# 09_USB_HDMI_sockets.net
KiCad netlist of a schematic drawn in Altium Designer
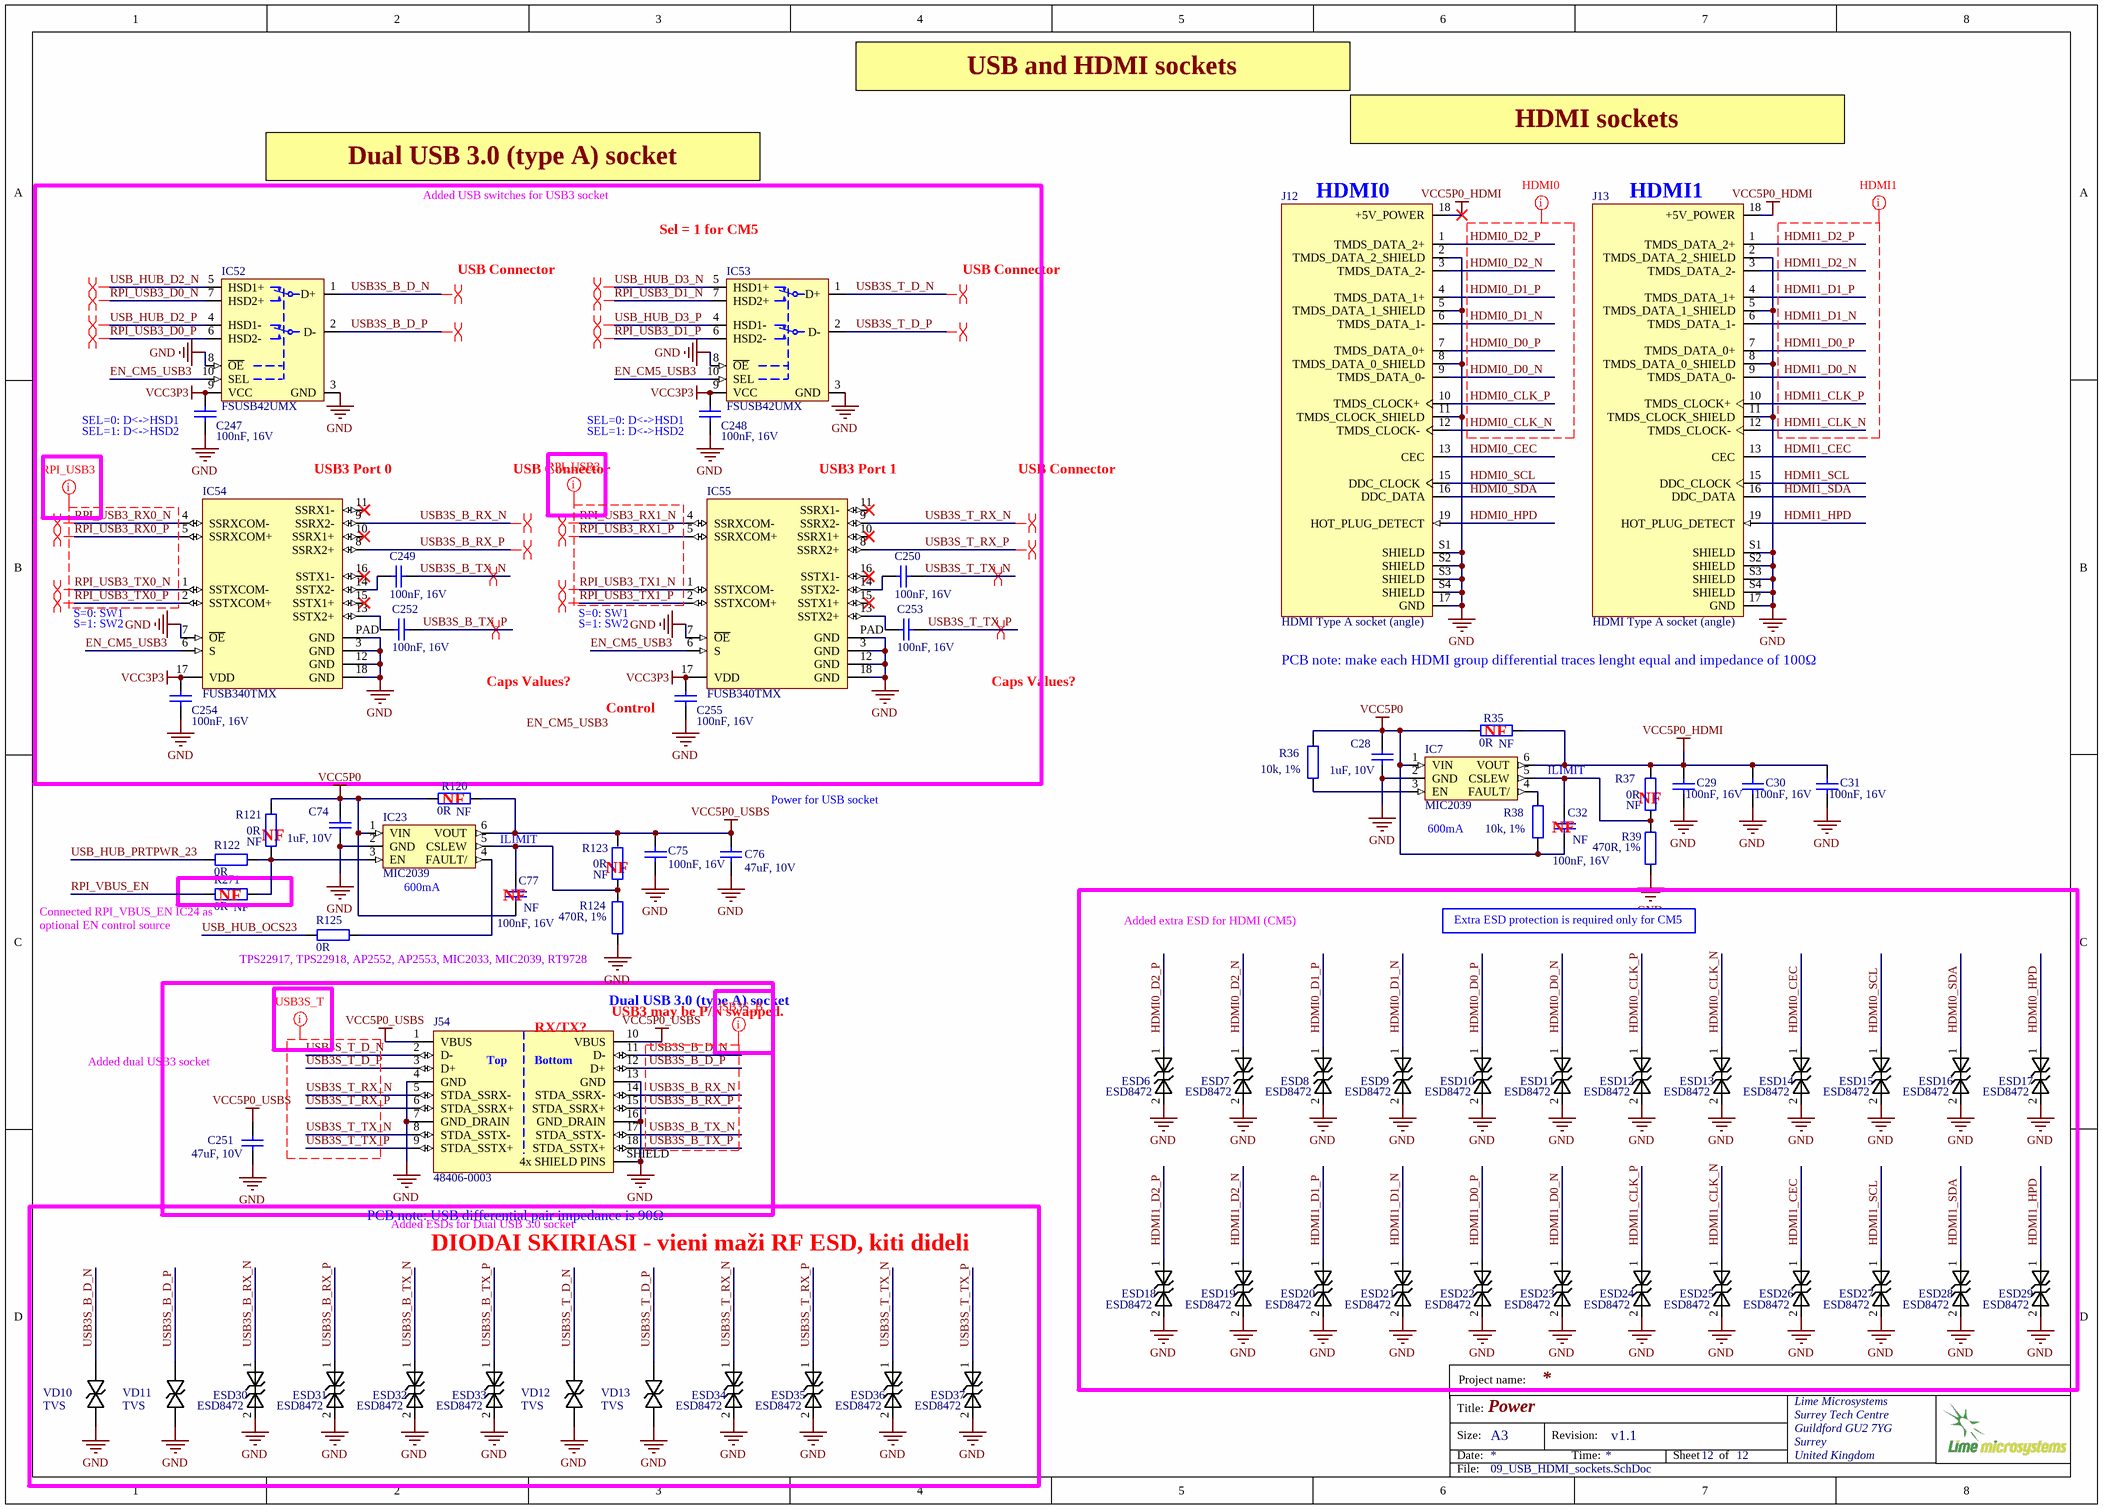
[diagram p0: 09_USB_HDMI_sockets.SchDoc]

(export (version "E")
  (design (tool "Eeschema 10.0.6"))
  (components
    (comp (ref "C28")
      (value "1uF, 10V")
      (footprint "CAP0402")
      (fields (field (name "MANUFACTURER") "Yageo"))
      (libsource (lib "") (part "Cap_0402_1"))
    )
    (comp (ref "C29")
      (value "100nF, 16V")
      (footprint "CAP0402")
      (fields
        (field (name "MANUFACTURER") "Murata Electronics")
        (field (name "TOLERANCE") "10 %")
        (field (name "MANUFACTURER PART NUMBER") "GRM155R71C104KA88D")
      )
      (libsource (lib "") (part "Cap_0402_1"))
    )
    (comp (ref "C30")
      (value "100nF, 16V")
      (footprint "CAP0402")
      (fields
        (field (name "MANUFACTURER") "Murata Electronics")
        (field (name "TOLERANCE") "10 %")
        (field (name "MANUFACTURER PART NUMBER") "GRM155R71C104KA88D")
      )
      (libsource (lib "") (part "Cap_0402_1"))
    )
    (comp (ref "C31")
      (value "100nF, 16V")
      (footprint "CAP0402")
      (fields
        (field (name "MANUFACTURER") "Murata Electronics")
        (field (name "TOLERANCE") "10 %")
        (field (name "MANUFACTURER PART NUMBER") "GRM155R71C104KA88D")
      )
      (libsource (lib "") (part "Cap_0402_1"))
    )
    (comp (ref "C32")
      (value "100nF, 16V")
      (footprint "CAP0402")
      (fields
        (field (name "ASSEMBLY INFO") "NF")
        (field (name "MANUFACTURER") "Murata Electronics")
        (field (name "TOLERANCE") "10 %")
        (field (name "MANUFACTURER PART NUMBER") "GRM155R71C104KA88D")
      )
      (libsource (lib "") (part "Cap_0402_1"))
    )
    (comp (ref "C74")
      (value "1uF, 10V")
      (footprint "CAP0402")
      (fields (field (name "MANUFACTURER") "Yageo"))
      (libsource (lib "") (part "Cap_0402_1"))
    )
    (comp (ref "C75")
      (value "100nF, 16V")
      (footprint "CAP0402")
      (fields
        (field (name "MANUFACTURER") "Murata Electronics")
        (field (name "TOLERANCE") "10 %")
        (field (name "MANUFACTURER PART NUMBER") "GRM155R71C104KA88D")
      )
      (libsource (lib "") (part "Cap_0402_1"))
    )
    (comp (ref "C76")
      (value "47uF, 10V")
      (footprint "CAP1206")
      (fields (field (name "TOLERANCE") "±20%") (field (name "MANUFACTURER") "TDK Corporation"))
      (libsource (lib "LimeFPGAboard_schLib") (part "Cap_1206"))
    )
    (comp (ref "C77")
      (value "100nF, 16V")
      (footprint "CAP0402")
      (fields
        (field (name "ASSEMBLY INFO") "NF")
        (field (name "MANUFACTURER") "Murata Electronics")
        (field (name "TOLERANCE") "10 %")
        (field (name "MANUFACTURER PART NUMBER") "GRM155R71C104KA88D")
      )
      (libsource (lib "") (part "Cap_0402_1"))
    )
    (comp (ref "C247")
      (value "100nF, 16V")
      (footprint "CAP0402")
      (fields
        (field (name "MANUFACTURER") "Murata Electronics")
        (field (name "TOLERANCE") "10 %")
        (field (name "MANUFACTURER PART NUMBER") "GRM155R71C104KA88D")
      )
      (libsource (lib "LimeMicroAltiumLib_schLib") (part "Cap_0402"))
    )
    (comp (ref "C248")
      (value "100nF, 16V")
      (footprint "CAP0402")
      (fields
        (field (name "MANUFACTURER") "Murata Electronics")
        (field (name "TOLERANCE") "10 %")
        (field (name "MANUFACTURER PART NUMBER") "GRM155R71C104KA88D")
      )
      (libsource (lib "LimeMicroAltiumLib_schLib") (part "Cap_0402"))
    )
    (comp (ref "C249")
      (value "100nF, 16V")
      (footprint "CAP0402")
      (fields
        (field (name "MANUFACTURER") "Murata Electronics")
        (field (name "TOLERANCE") "10 %")
        (field (name "MANUFACTURER PART NUMBER") "GRM155R71C104KA88D")
      )
      (libsource (lib "LimeMicroAltiumLib_schLib") (part "Cap_0402"))
    )
    (comp (ref "C250")
      (value "100nF, 16V")
      (footprint "CAP0402")
      (fields
        (field (name "MANUFACTURER") "Murata Electronics")
        (field (name "TOLERANCE") "10 %")
        (field (name "MANUFACTURER PART NUMBER") "GRM155R71C104KA88D")
      )
      (libsource (lib "LimeMicroAltiumLib_schLib") (part "Cap_0402"))
    )
    (comp (ref "C251")
      (value "47uF, 10V")
      (footprint "CAP1206")
      (fields (field (name "TOLERANCE") "±20%") (field (name "MANUFACTURER") "TDK Corporation"))
      (libsource (lib "LimeFPGAboard_schLib") (part "Cap_1206"))
    )
    (comp (ref "C252")
      (value "100nF, 16V")
      (footprint "CAP0402")
      (fields
        (field (name "MANUFACTURER") "Murata Electronics")
        (field (name "TOLERANCE") "10 %")
        (field (name "MANUFACTURER PART NUMBER") "GRM155R71C104KA88D")
      )
      (libsource (lib "LimeMicroAltiumLib_schLib") (part "Cap_0402"))
    )
    (comp (ref "C253")
      (value "100nF, 16V")
      (footprint "CAP0402")
      (fields
        (field (name "MANUFACTURER") "Murata Electronics")
        (field (name "TOLERANCE") "10 %")
        (field (name "MANUFACTURER PART NUMBER") "GRM155R71C104KA88D")
      )
      (libsource (lib "LimeMicroAltiumLib_schLib") (part "Cap_0402"))
    )
    (comp (ref "C254")
      (value "100nF, 16V")
      (footprint "CAP0402")
      (fields
        (field (name "MANUFACTURER") "Murata Electronics")
        (field (name "TOLERANCE") "10 %")
        (field (name "MANUFACTURER PART NUMBER") "GRM155R71C104KA88D")
      )
      (libsource (lib "LimeMicroAltiumLib_schLib") (part "Cap_0402"))
    )
    (comp (ref "C255")
      (value "100nF, 16V")
      (footprint "CAP0402")
      (fields
        (field (name "MANUFACTURER") "Murata Electronics")
        (field (name "TOLERANCE") "10 %")
        (field (name "MANUFACTURER PART NUMBER") "GRM155R71C104KA88D")
      )
      (libsource (lib "LimeMicroAltiumLib_schLib") (part "Cap_0402"))
    )
    (comp (ref "ESD6")
      (value "ESD8472")
      (footprint "ESD8472_X3DFN2")
      (fields (field (name "MANUFACTURER") "ON Semiconductor"))
      (libsource (lib "LimeMicroAltiumLib_schLib") (part "ESD8472"))
    )
    (comp (ref "ESD7")
      (value "ESD8472")
      (footprint "ESD8472_X3DFN2")
      (fields (field (name "MANUFACTURER") "ON Semiconductor"))
      (libsource (lib "LimeMicroAltiumLib_schLib") (part "ESD8472"))
    )
    (comp (ref "ESD8")
      (value "ESD8472")
      (footprint "ESD8472_X3DFN2")
      (fields (field (name "MANUFACTURER") "ON Semiconductor"))
      (libsource (lib "LimeMicroAltiumLib_schLib") (part "ESD8472"))
    )
    (comp (ref "ESD9")
      (value "ESD8472")
      (footprint "ESD8472_X3DFN2")
      (fields (field (name "MANUFACTURER") "ON Semiconductor"))
      (libsource (lib "LimeMicroAltiumLib_schLib") (part "ESD8472"))
    )
    (comp (ref "ESD10")
      (value "ESD8472")
      (footprint "ESD8472_X3DFN2")
      (fields (field (name "MANUFACTURER") "ON Semiconductor"))
      (libsource (lib "LimeMicroAltiumLib_schLib") (part "ESD8472"))
    )
    (comp (ref "ESD11")
      (value "ESD8472")
      (footprint "ESD8472_X3DFN2")
      (fields (field (name "MANUFACTURER") "ON Semiconductor"))
      (libsource (lib "LimeMicroAltiumLib_schLib") (part "ESD8472"))
    )
    (comp (ref "ESD12")
      (value "ESD8472")
      (footprint "ESD8472_X3DFN2")
      (fields (field (name "MANUFACTURER") "ON Semiconductor"))
      (libsource (lib "LimeMicroAltiumLib_schLib") (part "ESD8472"))
    )
    (comp (ref "ESD13")
      (value "ESD8472")
      (footprint "ESD8472_X3DFN2")
      (fields (field (name "MANUFACTURER") "ON Semiconductor"))
      (libsource (lib "LimeMicroAltiumLib_schLib") (part "ESD8472"))
    )
    (comp (ref "ESD14")
      (value "ESD8472")
      (footprint "ESD8472_X3DFN2")
      (fields (field (name "MANUFACTURER") "ON Semiconductor"))
      (libsource (lib "LimeMicroAltiumLib_schLib") (part "ESD8472"))
    )
    (comp (ref "ESD15")
      (value "ESD8472")
      (footprint "ESD8472_X3DFN2")
      (fields (field (name "MANUFACTURER") "ON Semiconductor"))
      (libsource (lib "LimeMicroAltiumLib_schLib") (part "ESD8472"))
    )
    (comp (ref "ESD16")
      (value "ESD8472")
      (footprint "ESD8472_X3DFN2")
      (fields (field (name "MANUFACTURER") "ON Semiconductor"))
      (libsource (lib "LimeMicroAltiumLib_schLib") (part "ESD8472"))
    )
    (comp (ref "ESD17")
      (value "ESD8472")
      (footprint "ESD8472_X3DFN2")
      (fields (field (name "MANUFACTURER") "ON Semiconductor"))
      (libsource (lib "LimeMicroAltiumLib_schLib") (part "ESD8472"))
    )
    (comp (ref "ESD18")
      (value "ESD8472")
      (footprint "ESD8472_X3DFN2")
      (fields (field (name "MANUFACTURER") "ON Semiconductor"))
      (libsource (lib "LimeMicroAltiumLib_schLib") (part "ESD8472"))
    )
    (comp (ref "ESD19")
      (value "ESD8472")
      (footprint "ESD8472_X3DFN2")
      (fields (field (name "MANUFACTURER") "ON Semiconductor"))
      (libsource (lib "LimeMicroAltiumLib_schLib") (part "ESD8472"))
    )
    (comp (ref "ESD20")
      (value "ESD8472")
      (footprint "ESD8472_X3DFN2")
      (fields (field (name "MANUFACTURER") "ON Semiconductor"))
      (libsource (lib "LimeMicroAltiumLib_schLib") (part "ESD8472"))
    )
    (comp (ref "ESD21")
      (value "ESD8472")
      (footprint "ESD8472_X3DFN2")
      (fields (field (name "MANUFACTURER") "ON Semiconductor"))
      (libsource (lib "LimeMicroAltiumLib_schLib") (part "ESD8472"))
    )
    (comp (ref "ESD22")
      (value "ESD8472")
      (footprint "ESD8472_X3DFN2")
      (fields (field (name "MANUFACTURER") "ON Semiconductor"))
      (libsource (lib "LimeMicroAltiumLib_schLib") (part "ESD8472"))
    )
    (comp (ref "ESD23")
      (value "ESD8472")
      (footprint "ESD8472_X3DFN2")
      (fields (field (name "MANUFACTURER") "ON Semiconductor"))
      (libsource (lib "LimeMicroAltiumLib_schLib") (part "ESD8472"))
    )
    (comp (ref "ESD24")
      (value "ESD8472")
      (footprint "ESD8472_X3DFN2")
      (fields (field (name "MANUFACTURER") "ON Semiconductor"))
      (libsource (lib "LimeMicroAltiumLib_schLib") (part "ESD8472"))
    )
    (comp (ref "ESD25")
      (value "ESD8472")
      (footprint "ESD8472_X3DFN2")
      (fields (field (name "MANUFACTURER") "ON Semiconductor"))
      (libsource (lib "LimeMicroAltiumLib_schLib") (part "ESD8472"))
    )
    (comp (ref "ESD26")
      (value "ESD8472")
      (footprint "ESD8472_X3DFN2")
      (fields (field (name "MANUFACTURER") "ON Semiconductor"))
      (libsource (lib "LimeMicroAltiumLib_schLib") (part "ESD8472"))
    )
    (comp (ref "ESD27")
      (value "ESD8472")
      (footprint "ESD8472_X3DFN2")
      (fields (field (name "MANUFACTURER") "ON Semiconductor"))
      (libsource (lib "LimeMicroAltiumLib_schLib") (part "ESD8472"))
    )
    (comp (ref "ESD28")
      (value "ESD8472")
      (footprint "ESD8472_X3DFN2")
      (fields (field (name "MANUFACTURER") "ON Semiconductor"))
      (libsource (lib "LimeMicroAltiumLib_schLib") (part "ESD8472"))
    )
    (comp (ref "ESD29")
      (value "ESD8472")
      (footprint "ESD8472_X3DFN2")
      (fields (field (name "MANUFACTURER") "ON Semiconductor"))
      (libsource (lib "LimeMicroAltiumLib_schLib") (part "ESD8472"))
    )
    (comp (ref "ESD30")
      (value "ESD8472")
      (footprint "ESD8472_X3DFN2")
      (fields (field (name "MANUFACTURER") "ON Semiconductor"))
      (libsource (lib "LimeMicroAltiumLib_schLib") (part "ESD8472"))
    )
    (comp (ref "ESD31")
      (value "ESD8472")
      (footprint "ESD8472_X3DFN2")
      (fields (field (name "MANUFACTURER") "ON Semiconductor"))
      (libsource (lib "LimeMicroAltiumLib_schLib") (part "ESD8472"))
    )
    (comp (ref "ESD32")
      (value "ESD8472")
      (footprint "ESD8472_X3DFN2")
      (fields (field (name "MANUFACTURER") "ON Semiconductor"))
      (libsource (lib "LimeMicroAltiumLib_schLib") (part "ESD8472"))
    )
    (comp (ref "ESD33")
      (value "ESD8472")
      (footprint "ESD8472_X3DFN2")
      (fields (field (name "MANUFACTURER") "ON Semiconductor"))
      (libsource (lib "LimeMicroAltiumLib_schLib") (part "ESD8472"))
    )
    (comp (ref "ESD34")
      (value "ESD8472")
      (footprint "ESD8472_X3DFN2")
      (fields (field (name "MANUFACTURER") "ON Semiconductor"))
      (libsource (lib "LimeMicroAltiumLib_schLib") (part "ESD8472"))
    )
    (comp (ref "ESD35")
      (value "ESD8472")
      (footprint "ESD8472_X3DFN2")
      (fields (field (name "MANUFACTURER") "ON Semiconductor"))
      (libsource (lib "LimeMicroAltiumLib_schLib") (part "ESD8472"))
    )
    (comp (ref "ESD36")
      (value "ESD8472")
      (footprint "ESD8472_X3DFN2")
      (fields (field (name "MANUFACTURER") "ON Semiconductor"))
      (libsource (lib "LimeMicroAltiumLib_schLib") (part "ESD8472"))
    )
    (comp (ref "ESD37")
      (value "ESD8472")
      (footprint "ESD8472_X3DFN2")
      (fields (field (name "MANUFACTURER") "ON Semiconductor"))
      (libsource (lib "LimeMicroAltiumLib_schLib") (part "ESD8472"))
    )
    (comp (ref "IC7")
      (value "MIC2039")
      (footprint "SOT23-6")
      (fields (field (name "MANUFACTURER") "Microchip"))
      (libsource (lib "LimeMicroAltiumLib_schLib_r04") (part "MIC2033_power_switch"))
    )
    (comp (ref "IC23")
      (value "MIC2039")
      (footprint "SOT23-6")
      (fields (field (name "MANUFACTURER") "Microchip"))
      (libsource (lib "LimeMicroAltiumLib_schLib_r04") (part "MIC2033_power_switch"))
    )
    (comp (ref "IC52")
      (value "FSUSB42UMX")
      (footprint "FSUSB42UMX")
      (fields (field (name "MANUFACTURER") "ON Semiconductor") (field (name "BASE PART NUMBER") "FSUSB42"))
      (libsource (lib "LimeMicroAltiumLib_schLib_r01") (part "FSUSB42UMX"))
    )
    (comp (ref "IC53")
      (value "FSUSB42UMX")
      (footprint "FSUSB42UMX")
      (fields (field (name "MANUFACTURER") "ON Semiconductor") (field (name "BASE PART NUMBER") "FSUSB42"))
      (libsource (lib "LimeMicroAltiumLib_schLib_r01") (part "FSUSB42UMX"))
    )
    (comp (ref "IC54")
      (value "FUSB340TMX")
      (footprint "FUSB340TMX_USB_switch_18-XFQFN")
      (fields (field (name "MANUFACTURER") "ON Semiconductor / Fairchild"))
      (libsource (lib "LimeMicroAltiumLib") (part "FUSB340TMX_USB_switch"))
    )
    (comp (ref "IC55")
      (value "FUSB340TMX")
      (footprint "FUSB340TMX_USB_switch_18-XFQFN")
      (fields (field (name "MANUFACTURER") "ON Semiconductor / Fairchild"))
      (libsource (lib "LimeMicroAltiumLib") (part "FUSB340TMX_USB_switch"))
    )
    (comp (ref "J12")
      (value "HDMI Type A socket (angle)")
      (footprint "HDMI_HD01-19-RA-TH")
      (fields (field (name "MANUFACTURER") "CUI Devices"))
      (libsource (lib "LimeMicroAltiumLib_schLib_r04") (part "HDMI_HD01-19-RA-TH"))
    )
    (comp (ref "J13")
      (value "HDMI Type A socket (angle)")
      (footprint "HDMI_HD01-19-RA-TH")
      (fields (field (name "MANUFACTURER") "CUI Devices"))
      (libsource (lib "LimeMicroAltiumLib_schLib_r04") (part "HDMI_HD01-19-RA-TH"))
    )
    (comp (ref "J54")
      (value "48406-0003")
      (footprint "Dual_USB_48406-0003_Molex")
      (fields (field (name "MANUFACTURER") "Molex"))
      (libsource (lib "LimeMicroAltiumLib") (part "Dual_USB_48406-0003_Molex"))
    )
    (comp (ref "R35")
      (value "0R")
      (footprint "RES0402")
      (fields
        (field (name "ASSEMBLY INFO") "NF")
        (field (name "MANUFACTURER") "Yageo")
        (field (name "TOLERANCE") "Jumper")
      )
      (libsource (lib "LimeMicroAltiumLib_schLib") (part "Res_0402"))
    )
    (comp (ref "R36")
      (value "10k, 1%")
      (footprint "RES0402")
      (fields (field (name "MANUFACTURER") "Yageo") (field (name "TOLERANCE") "±1%"))
      (libsource (lib "") (part "Res_0402_1"))
    )
    (comp (ref "R37")
      (value "0R")
      (footprint "RES0402")
      (fields
        (field (name "ASSEMBLY INFO") "NF")
        (field (name "MANUFACTURER") "Yageo")
        (field (name "TOLERANCE") "Jumper")
      )
      (libsource (lib "LimeMicroAltiumLib_schLib") (part "Res_0402"))
    )
    (comp (ref "R38")
      (value "10k, 1%")
      (footprint "RES0402")
      (fields (field (name "MANUFACTURER") "Yageo") (field (name "TOLERANCE") "±1%"))
      (libsource (lib "") (part "Res_0402_1"))
    )
    (comp (ref "R39")
      (value "470R, 1%")
      (footprint "RES0402")
      (fields (field (name "TOLERANCE") "1%") (field (name "MANUFACTURER") "Yageo"))
      (libsource (lib "LimeMicroAltiumLib_schLib") (part "Res_0402"))
    )
    (comp (ref "R120")
      (value "0R")
      (footprint "RES0402")
      (fields
        (field (name "ASSEMBLY INFO") "NF")
        (field (name "MANUFACTURER") "Yageo")
        (field (name "TOLERANCE") "Jumper")
      )
      (libsource (lib "LimeMicroAltiumLib_schLib") (part "Res_0402"))
    )
    (comp (ref "R121")
      (value "0R")
      (footprint "RES0402")
      (fields
        (field (name "ASSEMBLY INFO") "NF")
        (field (name "MANUFACTURER") "Yageo")
        (field (name "TOLERANCE") "Jumper")
      )
      (libsource (lib "LimeMicroAltiumLib_schLib") (part "Res_0402"))
    )
    (comp (ref "R122")
      (value "0R")
      (footprint "RES0402")
      (fields (field (name "MANUFACTURER") "Yageo") (field (name "TOLERANCE") "Jumper"))
      (libsource (lib "LimeMicroAltiumLib_schLib") (part "Res_0402"))
    )
    (comp (ref "R123")
      (value "0R")
      (footprint "RES0402")
      (fields
        (field (name "ASSEMBLY INFO") "NF")
        (field (name "MANUFACTURER") "Yageo")
        (field (name "TOLERANCE") "Jumper")
      )
      (libsource (lib "LimeMicroAltiumLib_schLib") (part "Res_0402"))
    )
    (comp (ref "R124")
      (value "470R, 1%")
      (footprint "RES0402")
      (fields (field (name "TOLERANCE") "1%") (field (name "MANUFACTURER") "Yageo"))
      (libsource (lib "LimeMicroAltiumLib_schLib") (part "Res_0402"))
    )
    (comp (ref "R125")
      (value "0R")
      (footprint "RES0402")
      (fields (field (name "MANUFACTURER") "Yageo") (field (name "TOLERANCE") "Jumper"))
      (libsource (lib "LimeMicroAltiumLib_schLib") (part "Res_0402"))
    )
    (comp (ref "R271")
      (value "0R")
      (footprint "RES0402")
      (fields
        (field (name "ASSEMBLY INFO") "NF")
        (field (name "MANUFACTURER") "Yageo")
        (field (name "TOLERANCE") "Jumper")
      )
      (libsource (lib "LimeMicroAltiumLib_schLib") (part "Res_0402"))
    )
    (comp (ref "VD10")
      (value "TVS")
      (footprint "SOD323")
      (fields
        (field (name "MANUFACTURER PART NUMBER") "SD03LCC")
        (field (name "MANUFACTURER") "Sangdest Microelectronics")
      )
      (libsource (lib "LimeNet-Micro_2v1-SDR") (part "DIODE_TVS"))
    )
    (comp (ref "VD11")
      (value "TVS")
      (footprint "SOD323")
      (fields
        (field (name "MANUFACTURER PART NUMBER") "SD03LCC")
        (field (name "MANUFACTURER") "Sangdest Microelectronics")
      )
      (libsource (lib "LimeNet-Micro_2v1-SDR") (part "DIODE_TVS"))
    )
    (comp (ref "VD12")
      (value "TVS")
      (footprint "SOD323")
      (fields
        (field (name "MANUFACTURER PART NUMBER") "SD03LCC")
        (field (name "MANUFACTURER") "Sangdest Microelectronics")
      )
      (libsource (lib "LimeNet-Micro_2v1-SDR") (part "DIODE_TVS"))
    )
    (comp (ref "VD13")
      (value "TVS")
      (footprint "SOD323")
      (fields
        (field (name "MANUFACTURER PART NUMBER") "SD03LCC")
        (field (name "MANUFACTURER") "Sangdest Microelectronics")
      )
      (libsource (lib "LimeNet-Micro_2v1-SDR") (part "DIODE_TVS"))
    )
  )
  (nets
    (net (code "1") (name "/EN_CM5_USB3") (class "Default")
      (node (ref "IC52") (pin "10") (pinfunction "SEL_10") (pintype "input"))
      (node (ref "IC53") (pin "10") (pinfunction "SEL_10") (pintype "input"))
      (node (ref "IC54") (pin "6") (pinfunction "S_6") (pintype "input"))
      (node (ref "IC55") (pin "6") (pinfunction "S_6") (pintype "input"))
    )
    (net (code "2") (name "/HDMI0_CEC") (class "Default")
      (node (ref "ESD14") (pin "1") (pinfunction "1_1") (pintype "passive"))
      (node (ref "J12") (pin "13") (pinfunction "CEC_13") (pintype "bidirectional"))
    )
    (net (code "3") (name "/HDMI0_CLK_N") (class "Default")
      (node (ref "ESD13") (pin "1") (pinfunction "1_1") (pintype "passive"))
      (node (ref "J12") (pin "12") (pinfunction "TMDS_CLOCK-_12") (pintype "bidirectional"))
    )
    (net (code "4") (name "/HDMI0_CLK_P") (class "Default")
      (node (ref "ESD12") (pin "1") (pinfunction "1_1") (pintype "passive"))
      (node (ref "J12") (pin "10") (pinfunction "TMDS_CLOCK+_10") (pintype "bidirectional"))
    )
    (net (code "5") (name "/HDMI0_D0_N") (class "Default")
      (node (ref "ESD11") (pin "1") (pinfunction "1_1") (pintype "passive"))
      (node (ref "J12") (pin "9") (pinfunction "TMDS_DATA_0-_9") (pintype "bidirectional"))
    )
    (net (code "6") (name "/HDMI0_D0_P") (class "Default")
      (node (ref "ESD10") (pin "1") (pinfunction "1_1") (pintype "passive"))
      (node (ref "J12") (pin "7") (pinfunction "TMDS_DATA_0+_7") (pintype "bidirectional"))
    )
    (net (code "7") (name "/HDMI0_D1_N") (class "Default")
      (node (ref "ESD9") (pin "1") (pinfunction "1_1") (pintype "passive"))
      (node (ref "J12") (pin "6") (pinfunction "TMDS_DATA_1-_6") (pintype "bidirectional"))
    )
    (net (code "8") (name "/HDMI0_D1_P") (class "Default")
      (node (ref "ESD8") (pin "1") (pinfunction "1_1") (pintype "passive"))
      (node (ref "J12") (pin "4") (pinfunction "TMDS_DATA_1+_4") (pintype "bidirectional"))
    )
    (net (code "9") (name "/HDMI0_D2_N") (class "Default")
      (node (ref "ESD7") (pin "1") (pinfunction "1_1") (pintype "passive"))
      (node (ref "J12") (pin "3") (pinfunction "TMDS_DATA_2-_3") (pintype "bidirectional"))
    )
    (net (code "10") (name "/HDMI0_D2_P") (class "Default")
      (node (ref "ESD6") (pin "1") (pinfunction "1_1") (pintype "passive"))
      (node (ref "J12") (pin "1") (pinfunction "TMDS_DATA_2+_1") (pintype "bidirectional"))
    )
    (net (code "11") (name "/HDMI0_HPD") (class "Default")
      (node (ref "ESD17") (pin "1") (pinfunction "1_1") (pintype "passive"))
      (node (ref "J12") (pin "19") (pinfunction "HOT_PLUG_DETECT_19") (pintype "input"))
    )
    (net (code "12") (name "/HDMI0_SCL") (class "Default")
      (node (ref "ESD15") (pin "1") (pinfunction "1_1") (pintype "passive"))
      (node (ref "J12") (pin "15") (pinfunction "DDC_CLOCK_15") (pintype "bidirectional"))
    )
    (net (code "13") (name "/HDMI0_SDA") (class "Default")
      (node (ref "ESD16") (pin "1") (pinfunction "1_1") (pintype "passive"))
      (node (ref "J12") (pin "16") (pinfunction "DDC_DATA_16") (pintype "bidirectional"))
    )
    (net (code "14") (name "/HDMI1_CEC") (class "Default")
      (node (ref "ESD26") (pin "1") (pinfunction "1_1") (pintype "passive"))
      (node (ref "J13") (pin "13") (pinfunction "CEC_13") (pintype "bidirectional"))
    )
    (net (code "15") (name "/HDMI1_CLK_N") (class "Default")
      (node (ref "ESD25") (pin "1") (pinfunction "1_1") (pintype "passive"))
      (node (ref "J13") (pin "12") (pinfunction "TMDS_CLOCK-_12") (pintype "bidirectional"))
    )
    (net (code "16") (name "/HDMI1_CLK_P") (class "Default")
      (node (ref "ESD24") (pin "1") (pinfunction "1_1") (pintype "passive"))
      (node (ref "J13") (pin "10") (pinfunction "TMDS_CLOCK+_10") (pintype "bidirectional"))
    )
    (net (code "17") (name "/HDMI1_D0_N") (class "Default")
      (node (ref "ESD23") (pin "1") (pinfunction "1_1") (pintype "passive"))
      (node (ref "J13") (pin "9") (pinfunction "TMDS_DATA_0-_9") (pintype "bidirectional"))
    )
    (net (code "18") (name "/HDMI1_D0_P") (class "Default")
      (node (ref "ESD22") (pin "1") (pinfunction "1_1") (pintype "passive"))
      (node (ref "J13") (pin "7") (pinfunction "TMDS_DATA_0+_7") (pintype "bidirectional"))
    )
    (net (code "19") (name "/HDMI1_D1_N") (class "Default")
      (node (ref "ESD21") (pin "1") (pinfunction "1_1") (pintype "passive"))
      (node (ref "J13") (pin "6") (pinfunction "TMDS_DATA_1-_6") (pintype "bidirectional"))
    )
    (net (code "20") (name "/HDMI1_D1_P") (class "Default")
      (node (ref "ESD20") (pin "1") (pinfunction "1_1") (pintype "passive"))
      (node (ref "J13") (pin "4") (pinfunction "TMDS_DATA_1+_4") (pintype "bidirectional"))
    )
    (net (code "21") (name "/HDMI1_D2_N") (class "Default")
      (node (ref "ESD19") (pin "1") (pinfunction "1_1") (pintype "passive"))
      (node (ref "J13") (pin "3") (pinfunction "TMDS_DATA_2-_3") (pintype "bidirectional"))
    )
    (net (code "22") (name "/HDMI1_D2_P") (class "Default")
      (node (ref "ESD18") (pin "1") (pinfunction "1_1") (pintype "passive"))
      (node (ref "J13") (pin "1") (pinfunction "TMDS_DATA_2+_1") (pintype "bidirectional"))
    )
    (net (code "23") (name "/HDMI1_HPD") (class "Default")
      (node (ref "ESD29") (pin "1") (pinfunction "1_1") (pintype "passive"))
      (node (ref "J13") (pin "19") (pinfunction "HOT_PLUG_DETECT_19") (pintype "input"))
    )
    (net (code "24") (name "/HDMI1_SCL") (class "Default")
      (node (ref "ESD27") (pin "1") (pinfunction "1_1") (pintype "passive"))
      (node (ref "J13") (pin "15") (pinfunction "DDC_CLOCK_15") (pintype "bidirectional"))
    )
    (net (code "25") (name "/HDMI1_SDA") (class "Default")
      (node (ref "ESD28") (pin "1") (pinfunction "1_1") (pintype "passive"))
      (node (ref "J13") (pin "16") (pinfunction "DDC_DATA_16") (pintype "bidirectional"))
    )
    (net (code "26") (name "/RPI_USB3_D0_N") (class "Default")
      (node (ref "IC52") (pin "7") (pinfunction "HSD2+_7") (pintype "passive"))
    )
    (net (code "27") (name "/RPI_USB3_D0_P") (class "Default")
      (node (ref "IC52") (pin "6") (pinfunction "HSD2-_6") (pintype "passive"))
    )
    (net (code "28") (name "/RPI_USB3_D1_N") (class "Default")
      (node (ref "IC53") (pin "7") (pinfunction "HSD2+_7") (pintype "passive"))
    )
    (net (code "29") (name "/RPI_USB3_D1_P") (class "Default")
      (node (ref "IC53") (pin "6") (pinfunction "HSD2-_6") (pintype "passive"))
    )
    (net (code "30") (name "/RPI_USB3_RX0_N") (class "Default")
      (node (ref "IC54") (pin "4") (pinfunction "SSRXCOM-_4") (pintype "bidirectional"))
    )
    (net (code "31") (name "/RPI_USB3_RX0_P") (class "Default")
      (node (ref "IC54") (pin "5") (pinfunction "SSRXCOM+_5") (pintype "bidirectional"))
    )
    (net (code "32") (name "/RPI_USB3_RX1_N") (class "Default")
      (node (ref "IC55") (pin "4") (pinfunction "SSRXCOM-_4") (pintype "bidirectional"))
    )
    (net (code "33") (name "/RPI_USB3_RX1_P") (class "Default")
      (node (ref "IC55") (pin "5") (pinfunction "SSRXCOM+_5") (pintype "bidirectional"))
    )
    (net (code "34") (name "/RPI_USB3_TX0_N") (class "Default")
      (node (ref "IC54") (pin "1") (pinfunction "SSTXCOM-_1") (pintype "bidirectional"))
    )
    (net (code "35") (name "/RPI_USB3_TX0_P") (class "Default")
      (node (ref "IC54") (pin "2") (pinfunction "SSTXCOM+_2") (pintype "bidirectional"))
    )
    (net (code "36") (name "/RPI_USB3_TX1_N") (class "Default")
      (node (ref "IC55") (pin "1") (pinfunction "SSTXCOM-_1") (pintype "bidirectional"))
    )
    (net (code "37") (name "/RPI_USB3_TX1_P") (class "Default")
      (node (ref "IC55") (pin "2") (pinfunction "SSTXCOM+_2") (pintype "bidirectional"))
    )
    (net (code "38") (name "/RPI_VBUS_EN") (class "Default")
      (node (ref "R271") (pin "2") (pinfunction "2_2") (pintype "passive"))
    )
    (net (code "39") (name "/USB3S_B_D_N") (class "Default")
      (node (ref "IC52") (pin "1") (pinfunction "D+_1") (pintype "passive"))
      (node (ref "J54") (pin "11") (pinfunction "D-_11") (pintype "bidirectional"))
      (node (ref "VD10") (pin "A") (pinfunction "A_A") (pintype "passive"))
    )
    (net (code "40") (name "/USB3S_B_D_P") (class "Default")
      (node (ref "IC52") (pin "2") (pinfunction "D-_2") (pintype "passive"))
      (node (ref "J54") (pin "12") (pinfunction "D+_12") (pintype "bidirectional"))
      (node (ref "VD11") (pin "A") (pinfunction "A_A") (pintype "passive"))
    )
    (net (code "41") (name "/USB3S_B_RX_N") (class "Default")
      (node (ref "ESD30") (pin "1") (pinfunction "1_1") (pintype "passive"))
      (node (ref "IC54") (pin "9") (pinfunction "SSRX2-_9") (pintype "bidirectional"))
      (node (ref "J54") (pin "14") (pinfunction "STDA_SSRX-_14") (pintype "bidirectional"))
    )
    (net (code "42") (name "/USB3S_B_RX_P") (class "Default")
      (node (ref "ESD31") (pin "1") (pinfunction "1_1") (pintype "passive"))
      (node (ref "IC54") (pin "8") (pinfunction "SSRX2+_8") (pintype "bidirectional"))
      (node (ref "J54") (pin "15") (pinfunction "STDA_SSRX+_15") (pintype "bidirectional"))
    )
    (net (code "43") (name "/USB3S_B_TX_N") (class "Default")
      (node (ref "C249") (pin "2") (pinfunction "2_2") (pintype "passive"))
      (node (ref "ESD32") (pin "1") (pinfunction "1_1") (pintype "passive"))
      (node (ref "J54") (pin "17") (pinfunction "STDA_SSTX-_17") (pintype "bidirectional"))
    )
    (net (code "44") (name "/USB3S_B_TX_P") (class "Default")
      (node (ref "C252") (pin "2") (pinfunction "2_2") (pintype "passive"))
      (node (ref "ESD33") (pin "1") (pinfunction "1_1") (pintype "passive"))
      (node (ref "J54") (pin "18") (pinfunction "STDA_SSTX+_18") (pintype "bidirectional"))
    )
    (net (code "45") (name "/USB3S_T_D_N") (class "Default")
      (node (ref "IC53") (pin "1") (pinfunction "D+_1") (pintype "passive"))
      (node (ref "J54") (pin "2") (pinfunction "D-_2") (pintype "bidirectional"))
      (node (ref "VD12") (pin "A") (pinfunction "A_A") (pintype "passive"))
    )
    (net (code "46") (name "/USB3S_T_D_P") (class "Default")
      (node (ref "IC53") (pin "2") (pinfunction "D-_2") (pintype "passive"))
      (node (ref "J54") (pin "3") (pinfunction "D+_3") (pintype "bidirectional"))
      (node (ref "VD13") (pin "A") (pinfunction "A_A") (pintype "passive"))
    )
    (net (code "47") (name "/USB3S_T_RX_N") (class "Default")
      (node (ref "ESD34") (pin "1") (pinfunction "1_1") (pintype "passive"))
      (node (ref "IC55") (pin "9") (pinfunction "SSRX2-_9") (pintype "bidirectional"))
      (node (ref "J54") (pin "5") (pinfunction "STDA_SSRX-_5") (pintype "bidirectional"))
    )
    (net (code "48") (name "/USB3S_T_RX_P") (class "Default")
      (node (ref "ESD35") (pin "1") (pinfunction "1_1") (pintype "passive"))
      (node (ref "IC55") (pin "8") (pinfunction "SSRX2+_8") (pintype "bidirectional"))
      (node (ref "J54") (pin "6") (pinfunction "STDA_SSRX+_6") (pintype "bidirectional"))
    )
    (net (code "49") (name "/USB3S_T_TX_N") (class "Default")
      (node (ref "C250") (pin "2") (pinfunction "2_2") (pintype "passive"))
      (node (ref "ESD36") (pin "1") (pinfunction "1_1") (pintype "passive"))
      (node (ref "J54") (pin "8") (pinfunction "STDA_SSTX-_8") (pintype "bidirectional"))
    )
    (net (code "50") (name "/USB3S_T_TX_P") (class "Default")
      (node (ref "C253") (pin "2") (pinfunction "2_2") (pintype "passive"))
      (node (ref "ESD37") (pin "1") (pinfunction "1_1") (pintype "passive"))
      (node (ref "J54") (pin "9") (pinfunction "STDA_SSTX+_9") (pintype "bidirectional"))
    )
    (net (code "51") (name "/USB_HUB_D2_N") (class "Default")
      (node (ref "IC52") (pin "5") (pinfunction "HSD1+_5") (pintype "passive"))
    )
    (net (code "52") (name "/USB_HUB_D2_P") (class "Default")
      (node (ref "IC52") (pin "4") (pinfunction "HSD1-_4") (pintype "passive"))
    )
    (net (code "53") (name "/USB_HUB_D3_N") (class "Default")
      (node (ref "IC53") (pin "5") (pinfunction "HSD1+_5") (pintype "passive"))
    )
    (net (code "54") (name "/USB_HUB_D3_P") (class "Default")
      (node (ref "IC53") (pin "4") (pinfunction "HSD1-_4") (pintype "passive"))
    )
    (net (code "55") (name "/USB_HUB_OCS23") (class "Default")
      (node (ref "R125") (pin "2") (pinfunction "2_2") (pintype "passive"))
    )
    (net (code "56") (name "/USB_HUB_PRTPWR_23") (class "Default")
      (node (ref "R122") (pin "2") (pinfunction "2_2") (pintype "passive"))
    )
    (net (code "57") (name "GND") (class "Default")
      (node (ref "C247") (pin "2") (pinfunction "2_2") (pintype "passive"))
      (node (ref "C248") (pin "2") (pinfunction "2_2") (pintype "passive"))
      (node (ref "C251") (pin "1") (pinfunction "1_1") (pintype "passive"))
      (node (ref "C254") (pin "2") (pinfunction "2_2") (pintype "passive"))
      (node (ref "C255") (pin "2") (pinfunction "2_2") (pintype "passive"))
      (node (ref "C28") (pin "2") (pinfunction "2_2") (pintype "passive"))
      (node (ref "C29") (pin "2") (pinfunction "2_2") (pintype "passive"))
      (node (ref "C30") (pin "2") (pinfunction "2_2") (pintype "passive"))
      (node (ref "C31") (pin "2") (pinfunction "2_2") (pintype "passive"))
      (node (ref "C74") (pin "2") (pinfunction "2_2") (pintype "passive"))
      (node (ref "C75") (pin "2") (pinfunction "2_2") (pintype "passive"))
      (node (ref "C76") (pin "1") (pinfunction "1_1") (pintype "passive"))
      (node (ref "ESD10") (pin "2") (pinfunction "2_2") (pintype "passive"))
      (node (ref "ESD11") (pin "2") (pinfunction "2_2") (pintype "passive"))
      (node (ref "ESD12") (pin "2") (pinfunction "2_2") (pintype "passive"))
      (node (ref "ESD13") (pin "2") (pinfunction "2_2") (pintype "passive"))
      (node (ref "ESD14") (pin "2") (pinfunction "2_2") (pintype "passive"))
      (node (ref "ESD15") (pin "2") (pinfunction "2_2") (pintype "passive"))
      (node (ref "ESD16") (pin "2") (pinfunction "2_2") (pintype "passive"))
      (node (ref "ESD17") (pin "2") (pinfunction "2_2") (pintype "passive"))
      (node (ref "ESD18") (pin "2") (pinfunction "2_2") (pintype "passive"))
      (node (ref "ESD19") (pin "2") (pinfunction "2_2") (pintype "passive"))
      (node (ref "ESD20") (pin "2") (pinfunction "2_2") (pintype "passive"))
      (node (ref "ESD21") (pin "2") (pinfunction "2_2") (pintype "passive"))
      (node (ref "ESD22") (pin "2") (pinfunction "2_2") (pintype "passive"))
      (node (ref "ESD23") (pin "2") (pinfunction "2_2") (pintype "passive"))
      (node (ref "ESD24") (pin "2") (pinfunction "2_2") (pintype "passive"))
      (node (ref "ESD25") (pin "2") (pinfunction "2_2") (pintype "passive"))
      (node (ref "ESD26") (pin "2") (pinfunction "2_2") (pintype "passive"))
      (node (ref "ESD27") (pin "2") (pinfunction "2_2") (pintype "passive"))
      (node (ref "ESD28") (pin "2") (pinfunction "2_2") (pintype "passive"))
      (node (ref "ESD29") (pin "2") (pinfunction "2_2") (pintype "passive"))
      (node (ref "ESD30") (pin "2") (pinfunction "2_2") (pintype "passive"))
      (node (ref "ESD31") (pin "2") (pinfunction "2_2") (pintype "passive"))
      (node (ref "ESD32") (pin "2") (pinfunction "2_2") (pintype "passive"))
      (node (ref "ESD33") (pin "2") (pinfunction "2_2") (pintype "passive"))
      (node (ref "ESD34") (pin "2") (pinfunction "2_2") (pintype "passive"))
      (node (ref "ESD35") (pin "2") (pinfunction "2_2") (pintype "passive"))
      (node (ref "ESD36") (pin "2") (pinfunction "2_2") (pintype "passive"))
      (node (ref "ESD37") (pin "2") (pinfunction "2_2") (pintype "passive"))
      (node (ref "ESD6") (pin "2") (pinfunction "2_2") (pintype "passive"))
      (node (ref "ESD7") (pin "2") (pinfunction "2_2") (pintype "passive"))
      (node (ref "ESD8") (pin "2") (pinfunction "2_2") (pintype "passive"))
      (node (ref "ESD9") (pin "2") (pinfunction "2_2") (pintype "passive"))
      (node (ref "IC23") (pin "2") (pinfunction "GND_2") (pintype "passive"))
      (node (ref "IC52") (pin "3") (pinfunction "GND_3") (pintype "passive"))
      (node (ref "IC52") (pin "8") (pinfunction "~{OE}_8") (pintype "input"))
      (node (ref "IC53") (pin "3") (pinfunction "GND_3") (pintype "passive"))
      (node (ref "IC53") (pin "8") (pinfunction "~{OE}_8") (pintype "input"))
      (node (ref "IC54") (pin "12") (pinfunction "GND_12") (pintype "passive"))
      (node (ref "IC54") (pin "18") (pinfunction "GND_18") (pintype "passive"))
      (node (ref "IC54") (pin "3") (pinfunction "GND_3") (pintype "passive"))
      (node (ref "IC54") (pin "7") (pinfunction "~{OE}_7") (pintype "input"))
      (node (ref "IC54") (pin "PAD") (pinfunction "GND_PAD") (pintype "passive"))
      (node (ref "IC55") (pin "12") (pinfunction "GND_12") (pintype "passive"))
      (node (ref "IC55") (pin "18") (pinfunction "GND_18") (pintype "passive"))
      (node (ref "IC55") (pin "3") (pinfunction "GND_3") (pintype "passive"))
      (node (ref "IC55") (pin "7") (pinfunction "~{OE}_7") (pintype "input"))
      (node (ref "IC55") (pin "PAD") (pinfunction "GND_PAD") (pintype "passive"))
      (node (ref "IC7") (pin "2") (pinfunction "GND_2") (pintype "passive"))
      (node (ref "J12") (pin "11") (pinfunction "TMDS_CLOCK_SHIELD_11") (pintype "passive"))
      (node (ref "J12") (pin "17") (pinfunction "GND_17") (pintype "power_in"))
      (node (ref "J12") (pin "2") (pinfunction "TMDS_DATA_2_SHIELD_2") (pintype "passive"))
      (node (ref "J12") (pin "5") (pinfunction "TMDS_DATA_1_SHIELD_5") (pintype "passive"))
      (node (ref "J12") (pin "8") (pinfunction "TMDS_DATA_0_SHIELD_8") (pintype "passive"))
      (node (ref "J12") (pin "S1") (pinfunction "SHIELD_S1") (pintype "passive"))
      (node (ref "J12") (pin "S2") (pinfunction "SHIELD_S2") (pintype "passive"))
      (node (ref "J12") (pin "S3") (pinfunction "SHIELD_S3") (pintype "passive"))
      (node (ref "J12") (pin "S4") (pinfunction "SHIELD_S4") (pintype "passive"))
      (node (ref "J13") (pin "11") (pinfunction "TMDS_CLOCK_SHIELD_11") (pintype "passive"))
      (node (ref "J13") (pin "17") (pinfunction "GND_17") (pintype "power_in"))
      (node (ref "J13") (pin "2") (pinfunction "TMDS_DATA_2_SHIELD_2") (pintype "passive"))
      (node (ref "J13") (pin "5") (pinfunction "TMDS_DATA_1_SHIELD_5") (pintype "passive"))
      (node (ref "J13") (pin "8") (pinfunction "TMDS_DATA_0_SHIELD_8") (pintype "passive"))
      (node (ref "J13") (pin "S1") (pinfunction "SHIELD_S1") (pintype "passive"))
      (node (ref "J13") (pin "S2") (pinfunction "SHIELD_S2") (pintype "passive"))
      (node (ref "J13") (pin "S3") (pinfunction "SHIELD_S3") (pintype "passive"))
      (node (ref "J13") (pin "S4") (pinfunction "SHIELD_S4") (pintype "passive"))
      (node (ref "J54") (pin "13") (pinfunction "GND_13") (pintype "passive"))
      (node (ref "J54") (pin "16") (pinfunction "GND_DRAIN_16") (pintype "passive"))
      (node (ref "J54") (pin "4") (pinfunction "GND_4") (pintype "passive"))
      (node (ref "J54") (pin "7") (pinfunction "GND_DRAIN_7") (pintype "passive"))
      (node (ref "J54") (pin "SHIELD") (pinfunction "4x_SHIELD_PINS_SHIELD") (pintype "passive"))
      (node (ref "R124") (pin "1") (pinfunction "1_1") (pintype "passive"))
      (node (ref "R39") (pin "1") (pinfunction "1_1") (pintype "passive"))
      (node (ref "VD10") (pin "K") (pinfunction "K_K") (pintype "passive"))
      (node (ref "VD11") (pin "K") (pinfunction "K_K") (pintype "passive"))
      (node (ref "VD12") (pin "K") (pinfunction "K_K") (pintype "passive"))
      (node (ref "VD13") (pin "K") (pinfunction "K_K") (pintype "passive"))
    )
    (net (code "58") (name "Net-(IC7-CSLEW)") (class "Default")
      (node (ref "C32") (pin "1") (pinfunction "1_1") (pintype "passive"))
      (node (ref "IC7") (pin "5") (pinfunction "CSLEW_5") (pintype "output"))
      (node (ref "R37") (pin "1") (pinfunction "1_1") (pintype "passive"))
      (node (ref "R39") (pin "2") (pinfunction "2_2") (pintype "passive"))
    )
    (net (code "59") (name "Net-(IC7-EN)") (class "Default")
      (node (ref "IC7") (pin "3") (pinfunction "EN_3") (pintype "input"))
      (node (ref "R36") (pin "1") (pinfunction "1_1") (pintype "passive"))
    )
    (net (code "60") (name "Net-(IC7-FAULT{slash})") (class "Default")
      (node (ref "IC7") (pin "4") (pinfunction "FAULT/_4") (pintype "output"))
      (node (ref "R38") (pin "2") (pinfunction "2_2") (pintype "passive"))
    )
    (net (code "61") (name "Net-(IC23-CSLEW)") (class "Default")
      (node (ref "C77") (pin "1") (pinfunction "1_1") (pintype "passive"))
      (node (ref "IC23") (pin "5") (pinfunction "CSLEW_5") (pintype "output"))
      (node (ref "R123") (pin "1") (pinfunction "1_1") (pintype "passive"))
      (node (ref "R124") (pin "2") (pinfunction "2_2") (pintype "passive"))
    )
    (net (code "62") (name "Net-(IC23-EN)") (class "Default")
      (node (ref "IC23") (pin "3") (pinfunction "EN_3") (pintype "input"))
      (node (ref "R121") (pin "1") (pinfunction "1_1") (pintype "passive"))
      (node (ref "R122") (pin "1") (pinfunction "1_1") (pintype "passive"))
      (node (ref "R271") (pin "1") (pinfunction "1_1") (pintype "passive"))
    )
    (net (code "63") (name "Net-(IC23-FAULT{slash})") (class "Default")
      (node (ref "IC23") (pin "4") (pinfunction "FAULT/_4") (pintype "output"))
      (node (ref "R125") (pin "1") (pinfunction "1_1") (pintype "passive"))
    )
    (net (code "64") (name "Net-(IC54-SSTX2+)") (class "Default")
      (node (ref "C252") (pin "1") (pinfunction "1_1") (pintype "passive"))
      (node (ref "IC54") (pin "13") (pinfunction "SSTX2+_13") (pintype "bidirectional"))
    )
    (net (code "65") (name "Net-(IC54-SSTX2-)") (class "Default")
      (node (ref "C249") (pin "1") (pinfunction "1_1") (pintype "passive"))
      (node (ref "IC54") (pin "14") (pinfunction "SSTX2-_14") (pintype "bidirectional"))
    )
    (net (code "66") (name "Net-(IC55-SSTX2+)") (class "Default")
      (node (ref "C253") (pin "1") (pinfunction "1_1") (pintype "passive"))
      (node (ref "IC55") (pin "13") (pinfunction "SSTX2+_13") (pintype "bidirectional"))
    )
    (net (code "67") (name "Net-(IC55-SSTX2-)") (class "Default")
      (node (ref "C250") (pin "1") (pinfunction "1_1") (pintype "passive"))
      (node (ref "IC55") (pin "14") (pinfunction "SSTX2-_14") (pintype "bidirectional"))
    )
    (net (code "68") (name "VCC3P3") (class "Default")
      (node (ref "C247") (pin "1") (pinfunction "1_1") (pintype "passive"))
      (node (ref "C248") (pin "1") (pinfunction "1_1") (pintype "passive"))
      (node (ref "C254") (pin "1") (pinfunction "1_1") (pintype "passive"))
      (node (ref "C255") (pin "1") (pinfunction "1_1") (pintype "passive"))
      (node (ref "IC52") (pin "9") (pinfunction "VCC_9") (pintype "power_in"))
      (node (ref "IC53") (pin "9") (pinfunction "VCC_9") (pintype "power_in"))
      (node (ref "IC54") (pin "17") (pinfunction "VDD_17") (pintype "power_in"))
      (node (ref "IC55") (pin "17") (pinfunction "VDD_17") (pintype "power_in"))
    )
    (net (code "69") (name "VCC5P0") (class "Default")
      (node (ref "C28") (pin "1") (pinfunction "1_1") (pintype "passive"))
      (node (ref "C32") (pin "2") (pinfunction "2_2") (pintype "passive"))
      (node (ref "C74") (pin "1") (pinfunction "1_1") (pintype "passive"))
      (node (ref "C77") (pin "2") (pinfunction "2_2") (pintype "passive"))
      (node (ref "IC23") (pin "1") (pinfunction "VIN_1") (pintype "input"))
      (node (ref "IC7") (pin "1") (pinfunction "VIN_1") (pintype "input"))
      (node (ref "R120") (pin "2") (pinfunction "2_2") (pintype "passive"))
      (node (ref "R121") (pin "2") (pinfunction "2_2") (pintype "passive"))
      (node (ref "R35") (pin "2") (pinfunction "2_2") (pintype "passive"))
      (node (ref "R36") (pin "2") (pinfunction "2_2") (pintype "passive"))
      (node (ref "R38") (pin "1") (pinfunction "1_1") (pintype "passive"))
    )
    (net (code "70") (name "VCC5P0_HDMI") (class "Default")
      (node (ref "C29") (pin "1") (pinfunction "1_1") (pintype "passive"))
      (node (ref "C30") (pin "1") (pinfunction "1_1") (pintype "passive"))
      (node (ref "C31") (pin "1") (pinfunction "1_1") (pintype "passive"))
      (node (ref "IC7") (pin "6") (pinfunction "VOUT_6") (pintype "output"))
      (node (ref "J12") (pin "18") (pinfunction "+5V_POWER_18") (pintype "power_in"))
      (node (ref "J13") (pin "18") (pinfunction "+5V_POWER_18") (pintype "power_in"))
      (node (ref "R35") (pin "1") (pinfunction "1_1") (pintype "passive"))
      (node (ref "R37") (pin "2") (pinfunction "2_2") (pintype "passive"))
    )
    (net (code "71") (name "VCC5P0_USBS") (class "Default")
      (node (ref "C251") (pin "2") (pinfunction "2_2") (pintype "passive"))
      (node (ref "C75") (pin "1") (pinfunction "1_1") (pintype "passive"))
      (node (ref "C76") (pin "2") (pinfunction "2_2") (pintype "passive"))
      (node (ref "IC23") (pin "6") (pinfunction "VOUT_6") (pintype "output"))
      (node (ref "J54") (pin "1") (pinfunction "VBUS_1") (pintype "power_in"))
      (node (ref "J54") (pin "10") (pinfunction "VBUS_10") (pintype "power_in"))
      (node (ref "R120") (pin "1") (pinfunction "1_1") (pintype "passive"))
      (node (ref "R123") (pin "2") (pinfunction "2_2") (pintype "passive"))
    )
    (net (code "72") (name "unconnected-(IC54-SSRX1+-Pad10)") (class "Default")
      (node (ref "IC54") (pin "10") (pinfunction "SSRX1+_10") (pintype "bidirectional+no_connect"))
    )
    (net (code "73") (name "unconnected-(IC54-SSRX1--Pad11)") (class "Default")
      (node (ref "IC54") (pin "11") (pinfunction "SSRX1-_11") (pintype "bidirectional+no_connect"))
    )
    (net (code "74") (name "unconnected-(IC54-SSTX1+-Pad15)") (class "Default")
      (node (ref "IC54") (pin "15") (pinfunction "SSTX1+_15") (pintype "bidirectional+no_connect"))
    )
    (net (code "75") (name "unconnected-(IC54-SSTX1--Pad16)") (class "Default")
      (node (ref "IC54") (pin "16") (pinfunction "SSTX1-_16") (pintype "bidirectional+no_connect"))
    )
    (net (code "76") (name "unconnected-(IC55-SSRX1+-Pad10)") (class "Default")
      (node (ref "IC55") (pin "10") (pinfunction "SSRX1+_10") (pintype "bidirectional+no_connect"))
    )
    (net (code "77") (name "unconnected-(IC55-SSRX1--Pad11)") (class "Default")
      (node (ref "IC55") (pin "11") (pinfunction "SSRX1-_11") (pintype "bidirectional+no_connect"))
    )
    (net (code "78") (name "unconnected-(IC55-SSTX1+-Pad15)") (class "Default")
      (node (ref "IC55") (pin "15") (pinfunction "SSTX1+_15") (pintype "bidirectional+no_connect"))
    )
    (net (code "79") (name "unconnected-(IC55-SSTX1--Pad16)") (class "Default")
      (node (ref "IC55") (pin "16") (pinfunction "SSTX1-_16") (pintype "bidirectional+no_connect"))
    )
  )
)
